# Camara_V4.net
KiCad netlist of a schematic drawn in EAGLE
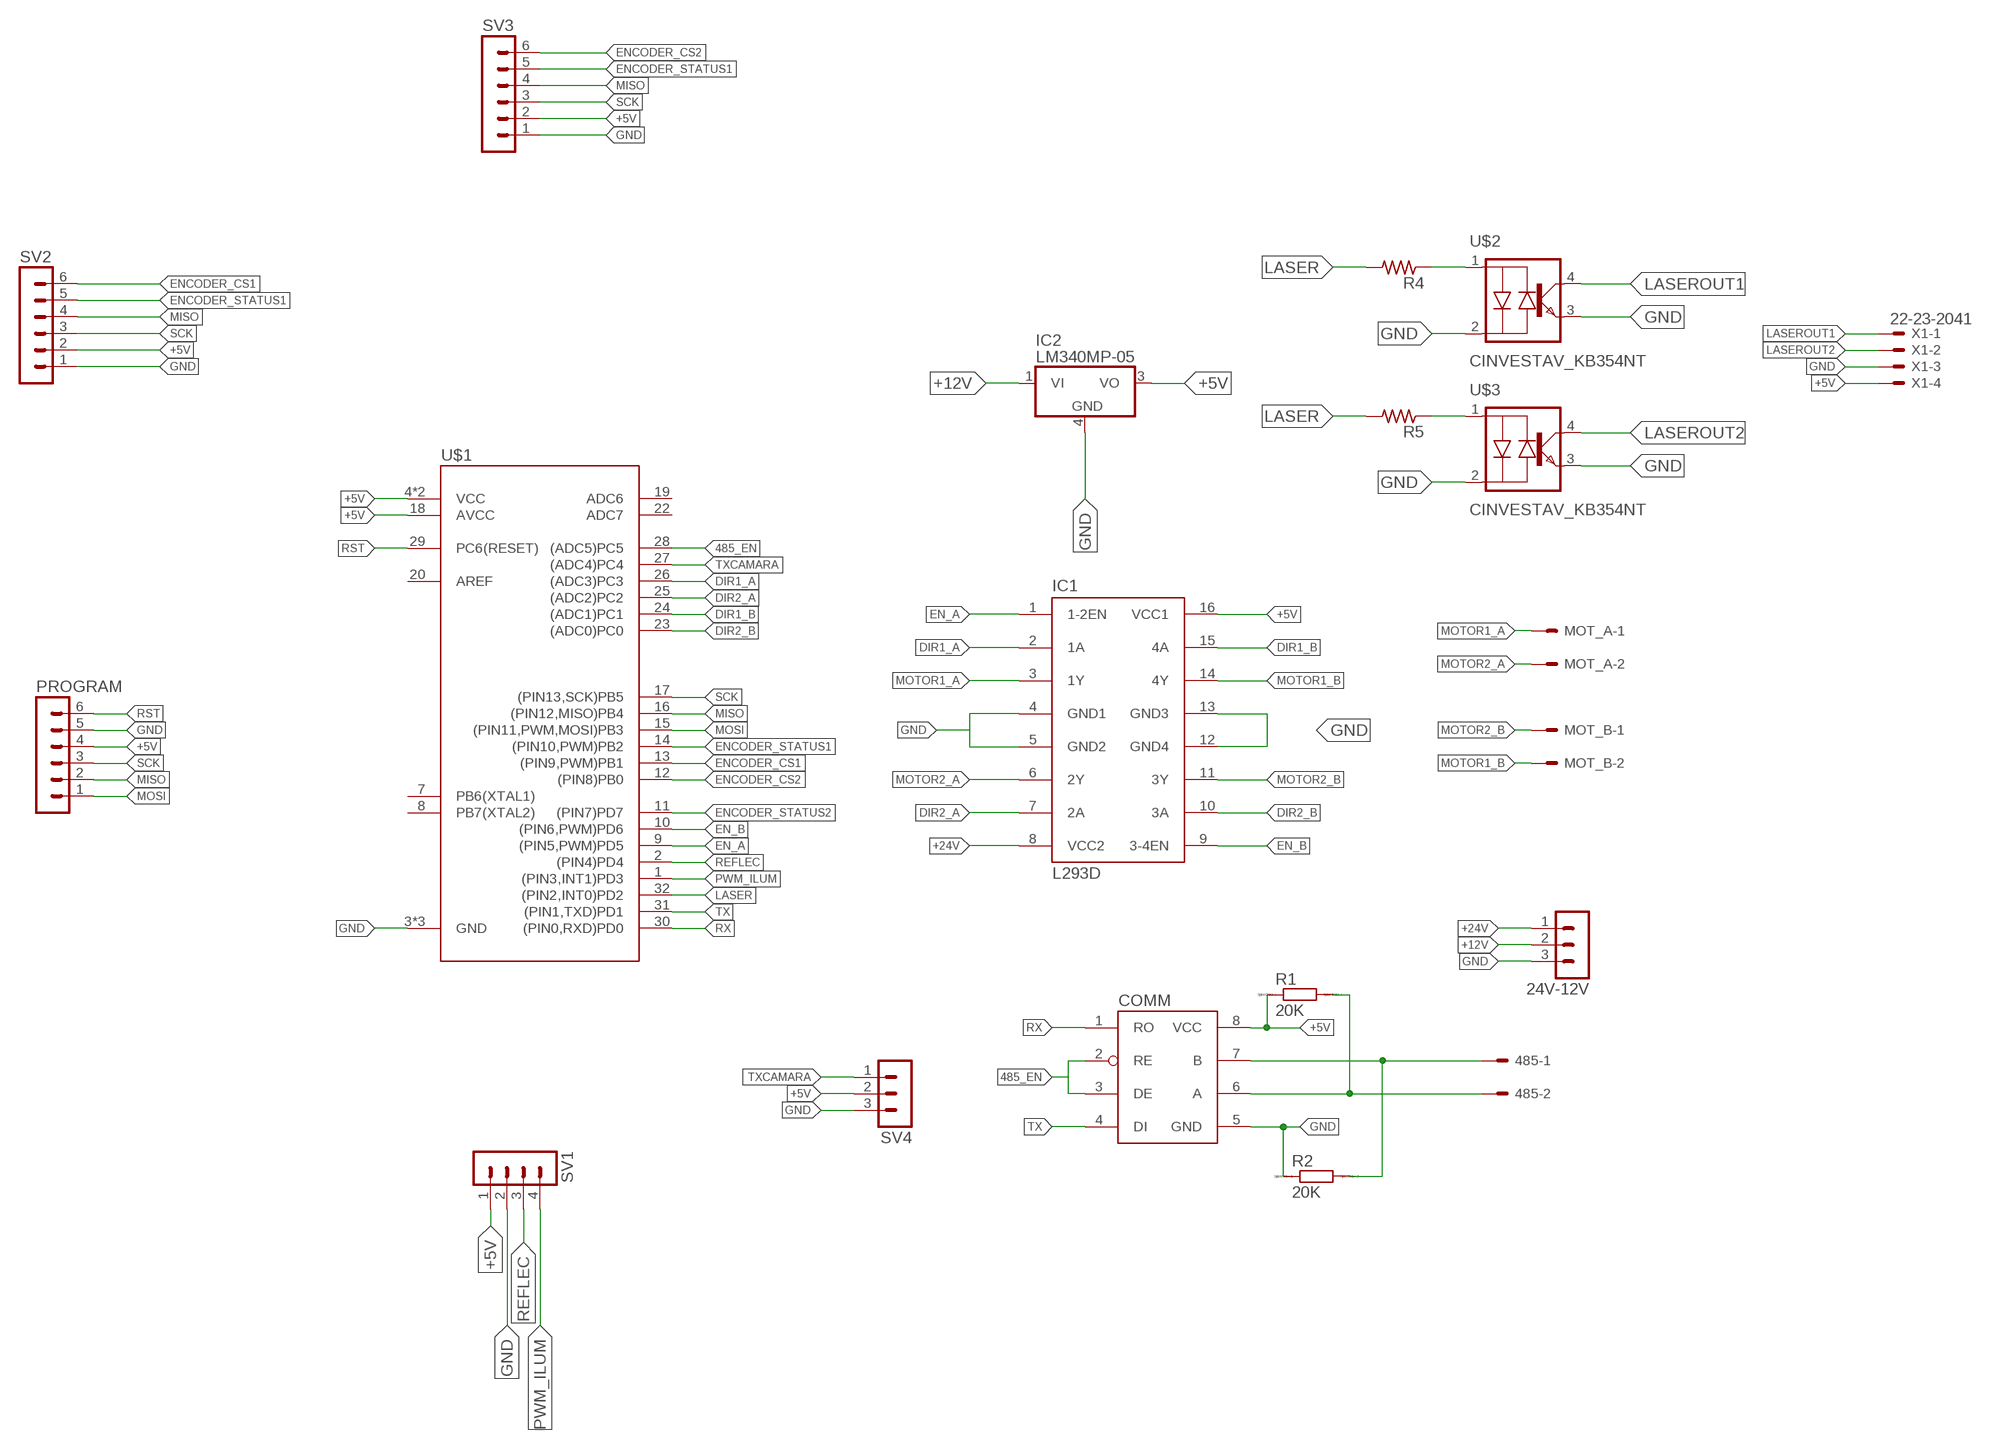
[diagram p0: schematic, sheet 1]

(export (version "E")
  (design (tool "Eeschema 10.0.6"))
  (components
    (comp (ref "24V-12V")
      (value "MA03-1")
      (footprint "eagle-import:MA03-1")
      (libsource (lib "eagle-import") (part "MA03-1"))
    )
    (comp (ref "485")
      (value "CINVESTAV_1X02")
      (footprint "eagle-import:CINVESTAV_1X02")
      (libsource (lib "eagle-import") (part "CINVESTAV_1X02"))
    )
    (comp (ref "COMM")
      (value "CINVESTAV_ADM1485")
      (footprint "eagle-import:CINVESTAV_SOIC8")
      (libsource (lib "eagle-import") (part "CINVESTAV_ADM1485"))
    )
    (comp (ref "IC1")
      (value "L293D")
      (footprint "eagle-import:DIL16")
      (libsource (lib "eagle-import") (part "L293D"))
    )
    (comp (ref "IC2")
      (value "LM340MP-05")
      (footprint "eagle-import:SOT223")
      (libsource (lib "eagle-import") (part "LM340?-MP05"))
    )
    (comp (ref "MOT_A")
      (value "CINVESTAV_1X02")
      (footprint "eagle-import:CINVESTAV_1X02")
      (libsource (lib "eagle-import") (part "CINVESTAV_1X02"))
    )
    (comp (ref "MOT_B")
      (value "CINVESTAV_1X02")
      (footprint "eagle-import:CINVESTAV_1X02")
      (libsource (lib "eagle-import") (part "CINVESTAV_1X02"))
    )
    (comp (ref "PROGRAM")
      (value "MA06-1")
      (footprint "eagle-import:MA06-1")
      (libsource (lib "eagle-import") (part "MA06-1"))
    )
    (comp (ref "R1")
      (value "20K")
      (footprint "eagle-import:R1206")
      (libsource (lib "eagle-import") (part "RR1206"))
    )
    (comp (ref "R2")
      (value "20K")
      (footprint "eagle-import:R1206")
      (libsource (lib "eagle-import") (part "RR1206"))
    )
    (comp (ref "R4")
      (value "R-US_M1206")
      (footprint "eagle-import:M1206")
      (libsource (lib "eagle-import") (part "R-US_M1206"))
    )
    (comp (ref "R5")
      (value "R-US_M1206")
      (footprint "eagle-import:M1206")
      (libsource (lib "eagle-import") (part "R-US_M1206"))
    )
    (comp (ref "SV1")
      (value "MA04-1")
      (footprint "eagle-import:MA04-1")
      (libsource (lib "eagle-import") (part "MA04-1"))
    )
    (comp (ref "SV2")
      (value "MA06-1")
      (footprint "eagle-import:MA06-1")
      (libsource (lib "eagle-import") (part "MA06-1"))
    )
    (comp (ref "SV3")
      (value "MA06-1")
      (footprint "eagle-import:MA06-1")
      (libsource (lib "eagle-import") (part "MA06-1"))
    )
    (comp (ref "SV4")
      (value "MA03-1")
      (footprint "eagle-import:MA03-1")
      (libsource (lib "eagle-import") (part "MA03-1"))
    )
    (comp (ref "U$1")
      (value "CINVESTAV_ATMEGA328")
      (footprint "eagle-import:CINVESTAV_TQFP32-08")
      (libsource (lib "eagle-import") (part "CINVESTAV_ATMEGA328"))
    )
    (comp (ref "U$2")
      (value "CINVESTAV_KB354NT")
      (footprint "eagle-import:CINVESTAV_SOIC4")
      (libsource (lib "eagle-import") (part "CINVESTAV_KB354NT"))
    )
    (comp (ref "U$3")
      (value "CINVESTAV_KB354NT")
      (footprint "eagle-import:CINVESTAV_SOIC4")
      (libsource (lib "eagle-import") (part "CINVESTAV_KB354NT"))
    )
    (comp (ref "X1")
      (value "22-23-2041")
      (footprint "eagle-import:22-23-2041")
      (fields (field (name "MF") "MOLEX"))
      (libsource (lib "eagle-import") (part "22-23-2041"))
    )
  )
  (nets
    (net (code "1") (name "+5V") (class "Default")
      (node (ref "COMM") (pin "8") (pinfunction "VCC_8") (pintype "power_in"))
      (node (ref "IC1") (pin "16") (pinfunction "VCC1_16") (pintype "power_in"))
      (node (ref "IC2") (pin "3") (pinfunction "VO_3") (pintype "passive"))
      (node (ref "PROGRAM") (pin "4") (pinfunction "4_4") (pintype "passive"))
      (node (ref "R1") (pin "1") (pinfunction "1_1") (pintype "passive"))
      (node (ref "SV1") (pin "1") (pinfunction "1_1") (pintype "passive"))
      (node (ref "SV2") (pin "2") (pinfunction "2_2") (pintype "passive"))
      (node (ref "SV3") (pin "2") (pinfunction "2_2") (pintype "passive"))
      (node (ref "SV4") (pin "2") (pinfunction "2_2") (pintype "passive"))
      (node (ref "U$1") (pin "18") (pinfunction "AVCC_18") (pintype "power_in"))
      (node (ref "U$1") (pin "4") (pinfunction "VCC_4") (pintype "power_in"))
      (node (ref "U$1") (pin "6") (pinfunction "VCC_6") (pintype "power_in"))
      (node (ref "X1") (pin "4") (pinfunction "S_4") (pintype "passive"))
    )
    (net (code "2") (name "+12V") (class "Default")
      (node (ref "24V-12V") (pin "2") (pinfunction "2_2") (pintype "passive"))
      (node (ref "IC2") (pin "1") (pinfunction "VI_1") (pintype "input"))
    )
    (net (code "3") (name "+24V") (class "Default")
      (node (ref "24V-12V") (pin "1") (pinfunction "1_1") (pintype "passive"))
      (node (ref "IC1") (pin "8") (pinfunction "VCC2_8") (pintype "power_in"))
    )
    (net (code "4") (name "485_EN") (class "Default")
      (node (ref "COMM") (pin "2") (pinfunction "RE_2") (pintype "input"))
      (node (ref "COMM") (pin "3") (pinfunction "DE_3") (pintype "input"))
      (node (ref "U$1") (pin "28") (pinfunction "(ADC5)PC5_28") (pintype "bidirectional"))
    )
    (net (code "5") (name "DIR1_A") (class "Default")
      (node (ref "IC1") (pin "2") (pinfunction "1A_2") (pintype "input"))
      (node (ref "U$1") (pin "26") (pinfunction "(ADC3)PC3_26") (pintype "bidirectional"))
    )
    (net (code "6") (name "DIR1_B") (class "Default")
      (node (ref "IC1") (pin "15") (pinfunction "4A_15") (pintype "input"))
      (node (ref "U$1") (pin "24") (pinfunction "(ADC1)PC1_24") (pintype "bidirectional"))
    )
    (net (code "7") (name "DIR2_A") (class "Default")
      (node (ref "IC1") (pin "7") (pinfunction "2A_7") (pintype "input"))
      (node (ref "U$1") (pin "25") (pinfunction "(ADC2)PC2_25") (pintype "bidirectional"))
    )
    (net (code "8") (name "DIR2_B") (class "Default")
      (node (ref "IC1") (pin "10") (pinfunction "3A_10") (pintype "input"))
      (node (ref "U$1") (pin "23") (pinfunction "(ADC0)PC0_23") (pintype "bidirectional"))
    )
    (net (code "9") (name "ENCODER_CS1") (class "Default")
      (node (ref "SV2") (pin "6") (pinfunction "6_6") (pintype "passive"))
      (node (ref "U$1") (pin "13") (pinfunction "(PIN9,PWM)PB1_13") (pintype "bidirectional"))
    )
    (net (code "10") (name "ENCODER_CS2") (class "Default")
      (node (ref "SV3") (pin "6") (pinfunction "6_6") (pintype "passive"))
      (node (ref "U$1") (pin "12") (pinfunction "(PIN8)PB0_12") (pintype "bidirectional"))
    )
    (net (code "11") (name "ENCODER_STATUS1") (class "Default")
      (node (ref "SV2") (pin "5") (pinfunction "5_5") (pintype "passive"))
      (node (ref "SV3") (pin "5") (pinfunction "5_5") (pintype "passive"))
      (node (ref "U$1") (pin "14") (pinfunction "(PIN10,PWM)PB2_14") (pintype "bidirectional"))
    )
    (net (code "12") (name "ENCODER_STATUS2") (class "Default")
      (node (ref "U$1") (pin "11") (pinfunction "(PIN7)PD7_11") (pintype "bidirectional"))
    )
    (net (code "13") (name "EN_A") (class "Default")
      (node (ref "IC1") (pin "1") (pinfunction "1-2EN_1") (pintype "input"))
      (node (ref "U$1") (pin "9") (pinfunction "(PIN5,PWM)PD5_9") (pintype "bidirectional"))
    )
    (net (code "14") (name "EN_B") (class "Default")
      (node (ref "IC1") (pin "9") (pinfunction "3-4EN_9") (pintype "input"))
      (node (ref "U$1") (pin "10") (pinfunction "(PIN6,PWM)PD6_10") (pintype "bidirectional"))
    )
    (net (code "15") (name "GND") (class "Default")
      (node (ref "24V-12V") (pin "3") (pinfunction "3_3") (pintype "passive"))
      (node (ref "COMM") (pin "5") (pinfunction "GND_5") (pintype "power_in"))
      (node (ref "IC1") (pin "12") (pinfunction "GND4_12") (pintype "power_in"))
      (node (ref "IC1") (pin "13") (pinfunction "GND3_13") (pintype "power_in"))
      (node (ref "IC1") (pin "4") (pinfunction "GND1_4") (pintype "power_in"))
      (node (ref "IC1") (pin "5") (pinfunction "GND2_5") (pintype "power_in"))
      (node (ref "IC2") (pin "4") (pinfunction "GND_4") (pintype "passive"))
      (node (ref "PROGRAM") (pin "5") (pinfunction "5_5") (pintype "passive"))
      (node (ref "R2") (pin "1") (pinfunction "1_1") (pintype "passive"))
      (node (ref "SV1") (pin "2") (pinfunction "2_2") (pintype "passive"))
      (node (ref "SV2") (pin "1") (pinfunction "1_1") (pintype "passive"))
      (node (ref "SV3") (pin "1") (pinfunction "1_1") (pintype "passive"))
      (node (ref "SV4") (pin "3") (pinfunction "3_3") (pintype "passive"))
      (node (ref "U$1") (pin "21") (pinfunction "GND_21") (pintype "power_in"))
      (node (ref "U$1") (pin "3") (pinfunction "GND_3") (pintype "power_in"))
      (node (ref "U$1") (pin "5") (pinfunction "GND_5") (pintype "power_in"))
      (node (ref "U$2") (pin "2") (pinfunction "C/A_2") (pintype "bidirectional"))
      (node (ref "U$2") (pin "3") (pinfunction "EMIT_3") (pintype "bidirectional"))
      (node (ref "U$3") (pin "2") (pinfunction "C/A_2") (pintype "bidirectional"))
      (node (ref "U$3") (pin "3") (pinfunction "EMIT_3") (pintype "bidirectional"))
      (node (ref "X1") (pin "3") (pinfunction "S_3") (pintype "passive"))
    )
    (net (code "16") (name "LASER") (class "Default")
      (node (ref "R4") (pin "2") (pinfunction "2_2") (pintype "passive"))
      (node (ref "R5") (pin "2") (pinfunction "2_2") (pintype "passive"))
      (node (ref "U$1") (pin "32") (pinfunction "(PIN2,INT0)PD2_32") (pintype "bidirectional"))
    )
    (net (code "17") (name "LASEROUT1") (class "Default")
      (node (ref "U$2") (pin "4") (pinfunction "COL_4") (pintype "bidirectional"))
      (node (ref "X1") (pin "1") (pinfunction "S_1") (pintype "passive"))
    )
    (net (code "18") (name "LASEROUT2") (class "Default")
      (node (ref "U$3") (pin "4") (pinfunction "COL_4") (pintype "bidirectional"))
      (node (ref "X1") (pin "2") (pinfunction "S_2") (pintype "passive"))
    )
    (net (code "19") (name "MISO") (class "Default")
      (node (ref "PROGRAM") (pin "2") (pinfunction "2_2") (pintype "passive"))
      (node (ref "SV2") (pin "4") (pinfunction "4_4") (pintype "passive"))
      (node (ref "SV3") (pin "4") (pinfunction "4_4") (pintype "passive"))
      (node (ref "U$1") (pin "16") (pinfunction "(PIN12,MISO)PB4_16") (pintype "bidirectional"))
    )
    (net (code "20") (name "MOSI") (class "Default")
      (node (ref "PROGRAM") (pin "1") (pinfunction "1_1") (pintype "passive"))
      (node (ref "U$1") (pin "15") (pinfunction "(PIN11,PWM,MOSI)PB3_15") (pintype "bidirectional"))
    )
    (net (code "21") (name "MOTOR1_A") (class "Default")
      (node (ref "IC1") (pin "3") (pinfunction "1Y_3") (pintype "output"))
      (node (ref "MOT_A") (pin "1") (pinfunction "S_1") (pintype "passive"))
    )
    (net (code "22") (name "MOTOR1_B") (class "Default")
      (node (ref "IC1") (pin "14") (pinfunction "4Y_14") (pintype "output"))
      (node (ref "MOT_B") (pin "2") (pinfunction "S_2") (pintype "passive"))
    )
    (net (code "23") (name "MOTOR2_A") (class "Default")
      (node (ref "IC1") (pin "6") (pinfunction "2Y_6") (pintype "output"))
      (node (ref "MOT_A") (pin "2") (pinfunction "S_2") (pintype "passive"))
    )
    (net (code "24") (name "MOTOR2_B") (class "Default")
      (node (ref "IC1") (pin "11") (pinfunction "3Y_11") (pintype "output"))
      (node (ref "MOT_B") (pin "1") (pinfunction "S_1") (pintype "passive"))
    )
    (net (code "25") (name "Net-(485A-S)") (class "Default")
      (node (ref "485") (pin "1") (pinfunction "S_1") (pintype "passive"))
      (node (ref "COMM") (pin "7") (pinfunction "B_7") (pintype "bidirectional"))
      (node (ref "R2") (pin "2") (pinfunction "2_2") (pintype "passive"))
    )
    (net (code "26") (name "Net-(485B-S)") (class "Default")
      (node (ref "485") (pin "2") (pinfunction "S_2") (pintype "passive"))
      (node (ref "COMM") (pin "6") (pinfunction "A_6") (pintype "bidirectional"))
      (node (ref "R1") (pin "2") (pinfunction "2_2") (pintype "passive"))
    )
    (net (code "27") (name "Net-(U$2-A{slash}C)") (class "Default")
      (node (ref "R4") (pin "1") (pinfunction "1_1") (pintype "passive"))
      (node (ref "U$2") (pin "1") (pinfunction "A/C_1") (pintype "bidirectional"))
    )
    (net (code "28") (name "Net-(U$3-A{slash}C)") (class "Default")
      (node (ref "R5") (pin "1") (pinfunction "1_1") (pintype "passive"))
      (node (ref "U$3") (pin "1") (pinfunction "A/C_1") (pintype "bidirectional"))
    )
    (net (code "29") (name "PWM_ILUM") (class "Default")
      (node (ref "SV1") (pin "4") (pinfunction "4_4") (pintype "passive"))
      (node (ref "U$1") (pin "1") (pinfunction "(PIN3,INT1)PD3_1") (pintype "bidirectional"))
    )
    (net (code "30") (name "REFLEC") (class "Default")
      (node (ref "SV1") (pin "3") (pinfunction "3_3") (pintype "passive"))
      (node (ref "U$1") (pin "2") (pinfunction "(PIN4)PD4_2") (pintype "bidirectional"))
    )
    (net (code "31") (name "RST") (class "Default")
      (node (ref "PROGRAM") (pin "6") (pinfunction "6_6") (pintype "passive"))
      (node (ref "U$1") (pin "29") (pinfunction "PC6(RESET)_29") (pintype "bidirectional"))
    )
    (net (code "32") (name "RX") (class "Default")
      (node (ref "COMM") (pin "1") (pinfunction "RO_1") (pintype "output"))
      (node (ref "U$1") (pin "30") (pinfunction "(PIN0,RXD)PD0_30") (pintype "bidirectional"))
    )
    (net (code "33") (name "SCK") (class "Default")
      (node (ref "PROGRAM") (pin "3") (pinfunction "3_3") (pintype "passive"))
      (node (ref "SV2") (pin "3") (pinfunction "3_3") (pintype "passive"))
      (node (ref "SV3") (pin "3") (pinfunction "3_3") (pintype "passive"))
      (node (ref "U$1") (pin "17") (pinfunction "(PIN13,SCK)PB5_17") (pintype "bidirectional"))
    )
    (net (code "34") (name "TX") (class "Default")
      (node (ref "COMM") (pin "4") (pinfunction "DI_4") (pintype "input"))
      (node (ref "U$1") (pin "31") (pinfunction "(PIN1,TXD)PD1_31") (pintype "bidirectional"))
    )
    (net (code "35") (name "TXCAMARA") (class "Default")
      (node (ref "SV4") (pin "1") (pinfunction "1_1") (pintype "passive"))
      (node (ref "U$1") (pin "27") (pinfunction "(ADC4)PC4_27") (pintype "bidirectional"))
    )
    (net (code "36") (name "unconnected-(U$1-ADC6-Pad19)") (class "Default")
      (node (ref "U$1") (pin "19") (pinfunction "ADC6_19") (pintype "bidirectional"))
    )
    (net (code "37") (name "unconnected-(U$1-ADC7-Pad22)") (class "Default")
      (node (ref "U$1") (pin "22") (pinfunction "ADC7_22") (pintype "bidirectional"))
    )
    (net (code "38") (name "unconnected-(U$1-AREF-Pad20)") (class "Default")
      (node (ref "U$1") (pin "20") (pinfunction "AREF_20") (pintype "passive"))
    )
    (net (code "39") (name "unconnected-(U$1-PB6(XTAL1)-Pad7)") (class "Default")
      (node (ref "U$1") (pin "7") (pinfunction "PB6(XTAL1)_7") (pintype "bidirectional"))
    )
    (net (code "40") (name "unconnected-(U$1-PB7(XTAL2)-Pad8)") (class "Default")
      (node (ref "U$1") (pin "8") (pinfunction "PB7(XTAL2)_8") (pintype "bidirectional"))
    )
  )
)
